# helloEcho___antonio_burrai.net
KiCad netlist of a schematic drawn in EAGLE
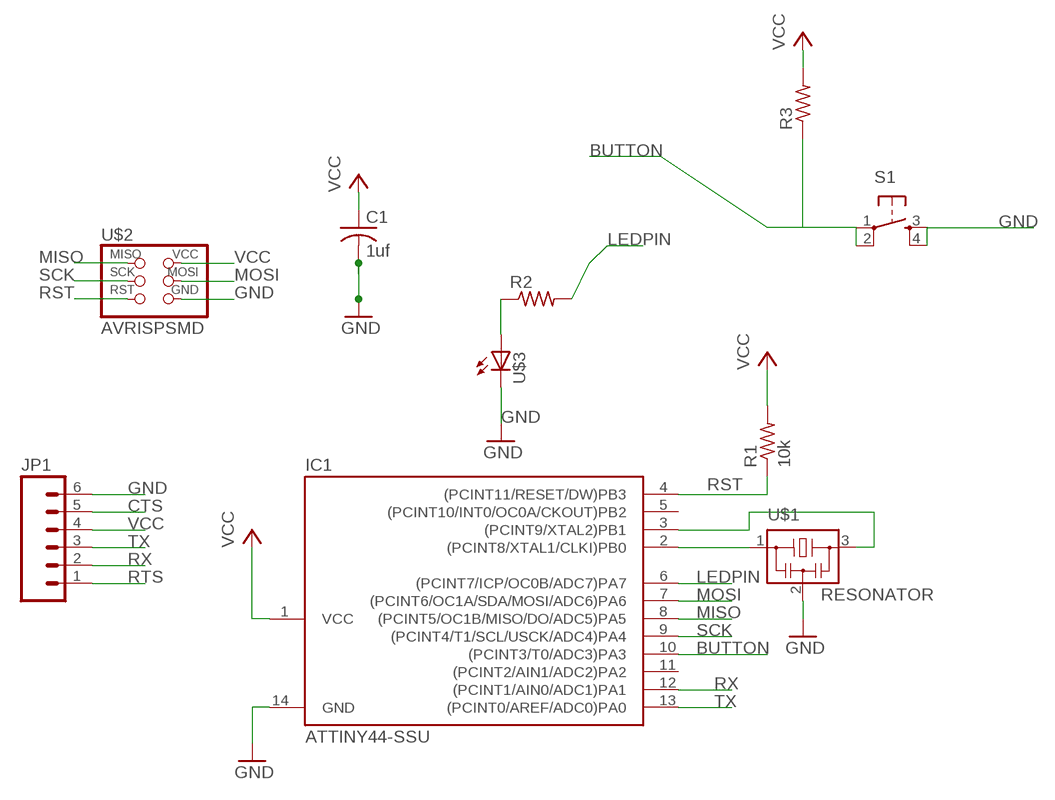
[diagram p0: schematic, sheet 1]

(export (version "E")
  (design (tool "Eeschema 10.0.6"))
  (components
    (comp (ref "C1")
      (value "1uf")
      (footprint "eagle-import:C1206")
      (libsource (lib "eagle-import") (part "C-USC1206"))
    )
    (comp (ref "IC1")
      (value "ATTINY44-SSU")
      (footprint "eagle-import:SOIC14")
      (libsource (lib "eagle-import") (part "ATTINY44-SSU"))
    )
    (comp (ref "JP1")
      (value "M06SMD")
      (footprint "eagle-import:1X06-SMD")
      (libsource (lib "eagle-import") (part "M06SMD"))
    )
    (comp (ref "R1")
      (value "10k")
      (footprint "eagle-import:R1206")
      (libsource (lib "eagle-import") (part "R-US_R1206"))
    )
    (comp (ref "R2")
      (value "RESISTOR1206")
      (footprint "eagle-import:1206")
      (libsource (lib "eagle-import") (part "RESISTOR1206"))
    )
    (comp (ref "R3")
      (value "RESISTOR1206")
      (footprint "eagle-import:1206")
      (libsource (lib "eagle-import") (part "RESISTOR1206"))
    )
    (comp (ref "S1")
      (value "6MM_SWITCH6MM_SWITCH")
      (footprint "eagle-import:6MM_SWITCH")
      (libsource (lib "eagle-import") (part "6MM_SWITCH6MM_SWITCH"))
    )
    (comp (ref "U$1")
      (value "RESONATOR")
      (footprint "eagle-import:EFOBM")
      (libsource (lib "eagle-import") (part "RESONATOR"))
    )
    (comp (ref "U$2")
      (value "AVRISPSMD")
      (footprint "eagle-import:2X03SMD")
      (libsource (lib "eagle-import") (part "AVRISPSMD"))
    )
    (comp (ref "U$3")
      (value "LED1206")
      (footprint "eagle-import:1206")
      (libsource (lib "eagle-import") (part "LED1206"))
    )
  )
  (nets
    (net (code "1") (name "/BUTTON") (class "Default")
      (node (ref "IC1") (pin "10") (pinfunction "(PCINT3/T0/ADC3)PA3_10") (pintype "bidirectional"))
      (node (ref "R3") (pin "1") (pinfunction "1_1") (pintype "passive"))
      (node (ref "S1") (pin "1") (pinfunction "P_1") (pintype "passive"))
      (node (ref "S1") (pin "2") (pinfunction "P1_2") (pintype "passive"))
    )
    (net (code "2") (name "/CTS") (class "Default")
      (node (ref "JP1") (pin "5") (pinfunction "5_5") (pintype "passive"))
    )
    (net (code "3") (name "/LEDPIN") (class "Default")
      (node (ref "IC1") (pin "6") (pinfunction "(PCINT7/ICP/OC0B/ADC7)PA7_6") (pintype "bidirectional"))
      (node (ref "R2") (pin "2") (pinfunction "2_2") (pintype "passive"))
    )
    (net (code "4") (name "/MISO") (class "Default")
      (node (ref "IC1") (pin "8") (pinfunction "(PCINT5/OC1B/MISO/DO/ADC5)PA5_8") (pintype "bidirectional"))
      (node (ref "U$2") (pin "1") (pinfunction "MISO_1") (pintype "passive"))
    )
    (net (code "5") (name "/MOSI") (class "Default")
      (node (ref "IC1") (pin "7") (pinfunction "(PCINT6/OC1A/SDA/MOSI/ADC6)PA6_7") (pintype "bidirectional"))
      (node (ref "U$2") (pin "4") (pinfunction "MOSI_4") (pintype "passive"))
    )
    (net (code "6") (name "/RST") (class "Default")
      (node (ref "IC1") (pin "4") (pinfunction "(PCINT11/RESET/DW)PB3_4") (pintype "bidirectional"))
      (node (ref "R1") (pin "1") (pinfunction "1_1") (pintype "passive"))
      (node (ref "U$2") (pin "5") (pinfunction "RST_5") (pintype "passive"))
    )
    (net (code "7") (name "/RTS") (class "Default")
      (node (ref "JP1") (pin "1") (pinfunction "1_1") (pintype "passive"))
    )
    (net (code "8") (name "/RX") (class "Default")
      (node (ref "IC1") (pin "12") (pinfunction "(PCINT1/AIN0/ADC1)PA1_12") (pintype "bidirectional"))
      (node (ref "JP1") (pin "2") (pinfunction "2_2") (pintype "passive"))
    )
    (net (code "9") (name "/SCK") (class "Default")
      (node (ref "IC1") (pin "9") (pinfunction "(PCINT4/T1/SCL/USCK/ADC4)PA4_9") (pintype "bidirectional"))
      (node (ref "U$2") (pin "3") (pinfunction "SCK_3") (pintype "passive"))
    )
    (net (code "10") (name "/TX") (class "Default")
      (node (ref "IC1") (pin "13") (pinfunction "(PCINT0/AREF/ADC0)PA0_13") (pintype "bidirectional"))
      (node (ref "JP1") (pin "3") (pinfunction "3_3") (pintype "passive"))
    )
    (net (code "11") (name "GND") (class "Default")
      (node (ref "C1") (pin "2") (pinfunction "2_2") (pintype "passive"))
      (node (ref "IC1") (pin "14") (pinfunction "GND_14") (pintype "power_in"))
      (node (ref "JP1") (pin "6") (pinfunction "6_6") (pintype "passive"))
      (node (ref "S1") (pin "3") (pinfunction "S_3") (pintype "passive"))
      (node (ref "S1") (pin "4") (pinfunction "S1_4") (pintype "passive"))
      (node (ref "U$1") (pin "2") (pinfunction "2_2") (pintype "passive"))
      (node (ref "U$2") (pin "6") (pinfunction "GND_6") (pintype "passive"))
      (node (ref "U$3") (pin "2") (pinfunction "C_2") (pintype "passive"))
    )
    (net (code "12") (name "Net-(IC1-(PCINT8{slash}XTAL1{slash}CLKI)PB0)") (class "Default")
      (node (ref "IC1") (pin "2") (pinfunction "(PCINT8/XTAL1/CLKI)PB0_2") (pintype "bidirectional"))
      (node (ref "U$1") (pin "1") (pinfunction "1_1") (pintype "passive"))
    )
    (net (code "13") (name "Net-(IC1-(PCINT9{slash}XTAL2)PB1)") (class "Default")
      (node (ref "IC1") (pin "3") (pinfunction "(PCINT9/XTAL2)PB1_3") (pintype "bidirectional"))
      (node (ref "U$1") (pin "3") (pinfunction "3_3") (pintype "passive"))
    )
    (net (code "14") (name "Net-(U$3-A)") (class "Default")
      (node (ref "R2") (pin "1") (pinfunction "1_1") (pintype "passive"))
      (node (ref "U$3") (pin "1") (pinfunction "A_1") (pintype "passive"))
    )
    (net (code "15") (name "VCC") (class "Default")
      (node (ref "C1") (pin "1") (pinfunction "1_1") (pintype "passive"))
      (node (ref "IC1") (pin "1") (pinfunction "VCC_1") (pintype "power_in"))
      (node (ref "JP1") (pin "4") (pinfunction "4_4") (pintype "passive"))
      (node (ref "R1") (pin "2") (pinfunction "2_2") (pintype "passive"))
      (node (ref "R3") (pin "2") (pinfunction "2_2") (pintype "passive"))
      (node (ref "U$2") (pin "2") (pinfunction "VCC_2") (pintype "passive"))
    )
    (net (code "16") (name "unconnected-(IC1-(PCINT2{slash}AIN1{slash}ADC2)PA2-Pad11)") (class "Default")
      (node (ref "IC1") (pin "11") (pinfunction "(PCINT2/AIN1/ADC2)PA2_11") (pintype "bidirectional"))
    )
    (net (code "17") (name "unconnected-(IC1-(PCINT10{slash}INT0{slash}OC0A{slash}CKOUT)PB2-Pad5)") (class "Default")
      (node (ref "IC1") (pin "5") (pinfunction "(PCINT10/INT0/OC0A/CKOUT)PB2_5") (pintype "bidirectional"))
    )
  )
)
